# Main_ASCII.net
KiCad netlist of a schematic drawn in Altium Designer
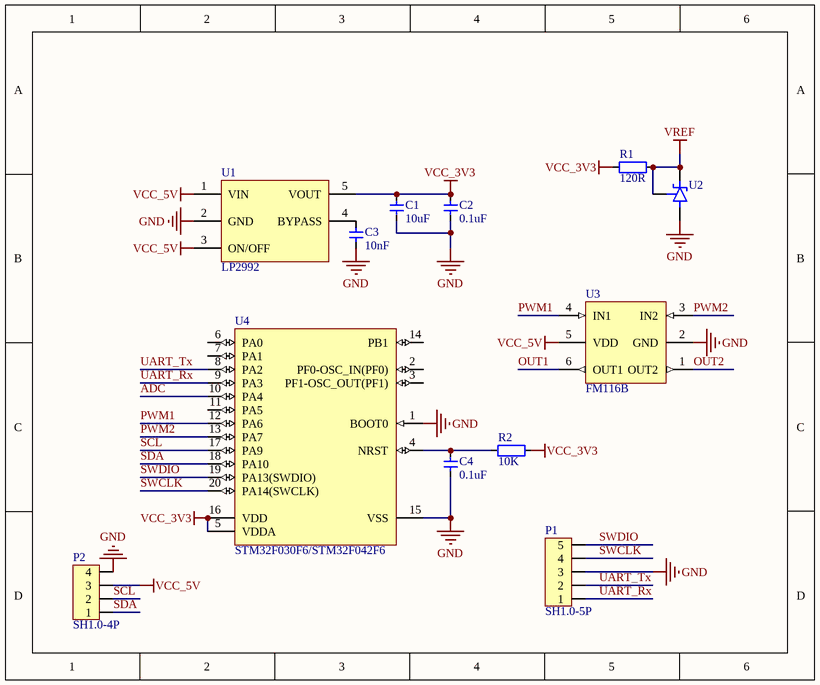
[diagram p0: Main_ASCII.SchDoc]

(export (version "E")
  (design (tool "Eeschema 10.0.6"))
  (components
    (comp (ref "C1")
      (value "10uF")
      (footprint "CAP_0402")
      (description "Capacitor")
      (libsource (lib "MyPcbLib") (part "电容-0402"))
    )
    (comp (ref "C2")
      (value "0.1uF")
      (footprint "CAP_0402")
      (description "Capacitor")
      (libsource (lib "MyPcbLib") (part "电容-0402"))
    )
    (comp (ref "C3")
      (value "10nF")
      (footprint "CAP_0402")
      (description "Capacitor")
      (libsource (lib "MyPcbLib") (part "电容-0402"))
    )
    (comp (ref "C4")
      (value "0.1uF")
      (footprint "CAP_0402")
      (description "Capacitor")
      (libsource (lib "MyPcbLib") (part "电容-0402"))
    )
    (comp (ref "P1") (value "SH1.0-5P") (footprint "SH1.0-5P") (libsource (lib "MyPcbLib") (part "SH1.0-5P")))
    (comp (ref "P2") (value "SH1.0-4P") (footprint "SH1.0-4P") (libsource (lib "MyPcbLib") (part "SH1.0-4P")))
    (comp (ref "R1")
      (value "120R")
      (footprint "RES_0402")
      (description "Resistor")
      (libsource (lib "") (part "电阻-0402_1"))
    )
    (comp (ref "R2")
      (value "10K")
      (footprint "RES_0402")
      (description "Resistor")
      (libsource (lib "MyPcbLib") (part "电阻-0402"))
    )
    (comp (ref "U1")
      (value "LP2992")
      (footprint "SOT23-5")
      (description "LDO")
      (libsource (lib "MyPcbLib") (part "LP2992"))
    )
    (comp (ref "U2")
      (value "TL431IDBZT")
      (footprint "SOT23-3")
      (description "Adjustable precision shunt regulator 3-SOT-23 -40 to 85")
      (fields (field (name "MF") "Texas Instruments"))
      (libsource (lib "MyPcbLib") (part "TL431IDBZT"))
    )
    (comp (ref "U3")
      (value "FM116B")
      (footprint "SOT23-6")
      (fields (field (name "PARTNUMBER") "24LC256-I/ST"))
      (libsource (lib "MyPcbLib") (part "FM116B"))
    )
    (comp (ref "U4")
      (value "STM32F030F6/STM32F042F6")
      (footprint "TSSOP-20")
      (fields (field (name "PARTNUMBER") "STM32F030F4P6"))
      (libsource (lib "MyPcbLib") (part "STM32F030F4P6"))
    )
  )
  (nets
    (net (code "1") (name "/ADC") (class "Default")
      (node (ref "U4") (pin "10") (pinfunction "PA4_10") (pintype "bidirectional"))
    )
    (net (code "2") (name "/OUT1") (class "Default")
      (node (ref "U3") (pin "6") (pinfunction "OUT1_6") (pintype "output"))
    )
    (net (code "3") (name "/OUT2") (class "Default")
      (node (ref "U3") (pin "1") (pinfunction "OUT2_1") (pintype "output"))
    )
    (net (code "4") (name "/PWM1") (class "Default")
      (node (ref "U3") (pin "4") (pinfunction "IN1_4") (pintype "input"))
      (node (ref "U4") (pin "12") (pinfunction "PA6_12") (pintype "bidirectional"))
    )
    (net (code "5") (name "/PWM2") (class "Default")
      (node (ref "U3") (pin "3") (pinfunction "IN2_3") (pintype "input"))
      (node (ref "U4") (pin "13") (pinfunction "PA7_13") (pintype "bidirectional"))
    )
    (net (code "6") (name "/SCL") (class "Default")
      (node (ref "P2") (pin "2") (pinfunction "2_2") (pintype "passive"))
      (node (ref "U4") (pin "17") (pinfunction "PA9_17") (pintype "bidirectional"))
    )
    (net (code "7") (name "/SDA") (class "Default")
      (node (ref "P2") (pin "1") (pinfunction "1_1") (pintype "passive"))
      (node (ref "U4") (pin "18") (pinfunction "PA10_18") (pintype "bidirectional"))
    )
    (net (code "8") (name "/SWCLK") (class "Default")
      (node (ref "P1") (pin "4") (pinfunction "4_4") (pintype "passive"))
      (node (ref "U4") (pin "20") (pinfunction "PA14(SWCLK)_20") (pintype "bidirectional"))
    )
    (net (code "9") (name "/SWDIO") (class "Default")
      (node (ref "P1") (pin "5") (pinfunction "5_5") (pintype "passive"))
      (node (ref "U4") (pin "19") (pinfunction "PA13(SWDIO)_19") (pintype "bidirectional"))
    )
    (net (code "10") (name "/UART_Rx") (class "Default")
      (node (ref "P1") (pin "1") (pinfunction "1_1") (pintype "passive"))
      (node (ref "U4") (pin "9") (pinfunction "PA3_9") (pintype "bidirectional"))
    )
    (net (code "11") (name "/UART_Tx") (class "Default")
      (node (ref "P1") (pin "2") (pinfunction "2_2") (pintype "passive"))
      (node (ref "U4") (pin "8") (pinfunction "PA2_8") (pintype "bidirectional"))
    )
    (net (code "12") (name "GND") (class "Default")
      (node (ref "C1") (pin "1") (pinfunction "1_1") (pintype "passive"))
      (node (ref "C2") (pin "1") (pinfunction "1_1") (pintype "passive"))
      (node (ref "C3") (pin "2") (pinfunction "2_2") (pintype "passive"))
      (node (ref "C4") (pin "1") (pinfunction "1_1") (pintype "passive"))
      (node (ref "P1") (pin "3") (pinfunction "3_3") (pintype "passive"))
      (node (ref "P2") (pin "4") (pinfunction "4_4") (pintype "passive"))
      (node (ref "U1") (pin "2") (pinfunction "GND_2") (pintype "passive"))
      (node (ref "U2") (pin "3") (pinfunction "ANODE_3") (pintype "passive"))
      (node (ref "U3") (pin "2") (pinfunction "GND_2") (pintype "power_in"))
      (node (ref "U4") (pin "1") (pinfunction "BOOT0_1") (pintype "input"))
      (node (ref "U4") (pin "15") (pinfunction "VSS_15") (pintype "power_in"))
    )
    (net (code "13") (name "Net-(U1-BYPASS)") (class "Default")
      (node (ref "C3") (pin "1") (pinfunction "1_1") (pintype "passive"))
      (node (ref "U1") (pin "4") (pinfunction "BYPASS_4") (pintype "passive"))
    )
    (net (code "14") (name "Net-(U4-NRST)") (class "Default")
      (node (ref "C4") (pin "2") (pinfunction "2_2") (pintype "passive"))
      (node (ref "R2") (pin "2") (pinfunction "2_2") (pintype "passive"))
      (node (ref "U4") (pin "4") (pinfunction "NRST_4") (pintype "bidirectional"))
    )
    (net (code "15") (name "VCC_3V3") (class "Default")
      (node (ref "C1") (pin "2") (pinfunction "2_2") (pintype "passive"))
      (node (ref "C2") (pin "2") (pinfunction "2_2") (pintype "passive"))
      (node (ref "R1") (pin "1") (pinfunction "1_1") (pintype "passive"))
      (node (ref "R2") (pin "1") (pinfunction "1_1") (pintype "passive"))
      (node (ref "U1") (pin "5") (pinfunction "VOUT_5") (pintype "passive"))
      (node (ref "U4") (pin "16") (pinfunction "VDD_16") (pintype "power_in"))
      (node (ref "U4") (pin "5") (pinfunction "VDDA_5") (pintype "power_in"))
    )
    (net (code "16") (name "VCC_5V") (class "Default")
      (node (ref "P2") (pin "3") (pinfunction "3_3") (pintype "passive"))
      (node (ref "U1") (pin "1") (pinfunction "VIN_1") (pintype "passive"))
      (node (ref "U1") (pin "3") (pinfunction "ON/OFF_3") (pintype "passive"))
      (node (ref "U3") (pin "5") (pinfunction "VDD_5") (pintype "power_in"))
    )
    (net (code "17") (name "VREF") (class "Default")
      (node (ref "R1") (pin "2") (pinfunction "2_2") (pintype "passive"))
      (node (ref "U2") (pin "1") (pinfunction "CATHODE_1") (pintype "passive"))
      (node (ref "U2") (pin "2") (pinfunction "REF_2") (pintype "passive"))
    )
    (net (code "18") (name "unconnected-(U4-PA0-Pad6)") (class "Default")
      (node (ref "U4") (pin "6") (pinfunction "PA0_6") (pintype "bidirectional"))
    )
    (net (code "19") (name "unconnected-(U4-PA1-Pad7)") (class "Default")
      (node (ref "U4") (pin "7") (pinfunction "PA1_7") (pintype "bidirectional"))
    )
    (net (code "20") (name "unconnected-(U4-PA5-Pad11)") (class "Default")
      (node (ref "U4") (pin "11") (pinfunction "PA5_11") (pintype "bidirectional"))
    )
    (net (code "21") (name "unconnected-(U4-PB1-Pad14)") (class "Default")
      (node (ref "U4") (pin "14") (pinfunction "PB1_14") (pintype "bidirectional"))
    )
    (net (code "22") (name "unconnected-(U4-PF0-OSC_IN(PF0)-Pad2)") (class "Default")
      (node (ref "U4") (pin "2") (pinfunction "PF0-OSC_IN(PF0)_2") (pintype "bidirectional"))
    )
    (net (code "23") (name "unconnected-(U4-PF1-OSC_OUT(PF1)-Pad3)") (class "Default")
      (node (ref "U4") (pin "3") (pinfunction "PF1-OSC_OUT(PF1)_3") (pintype "bidirectional"))
    )
  )
)
